# MIPI-Bridge.net
KiCad netlist of a schematic drawn in Altium Designer
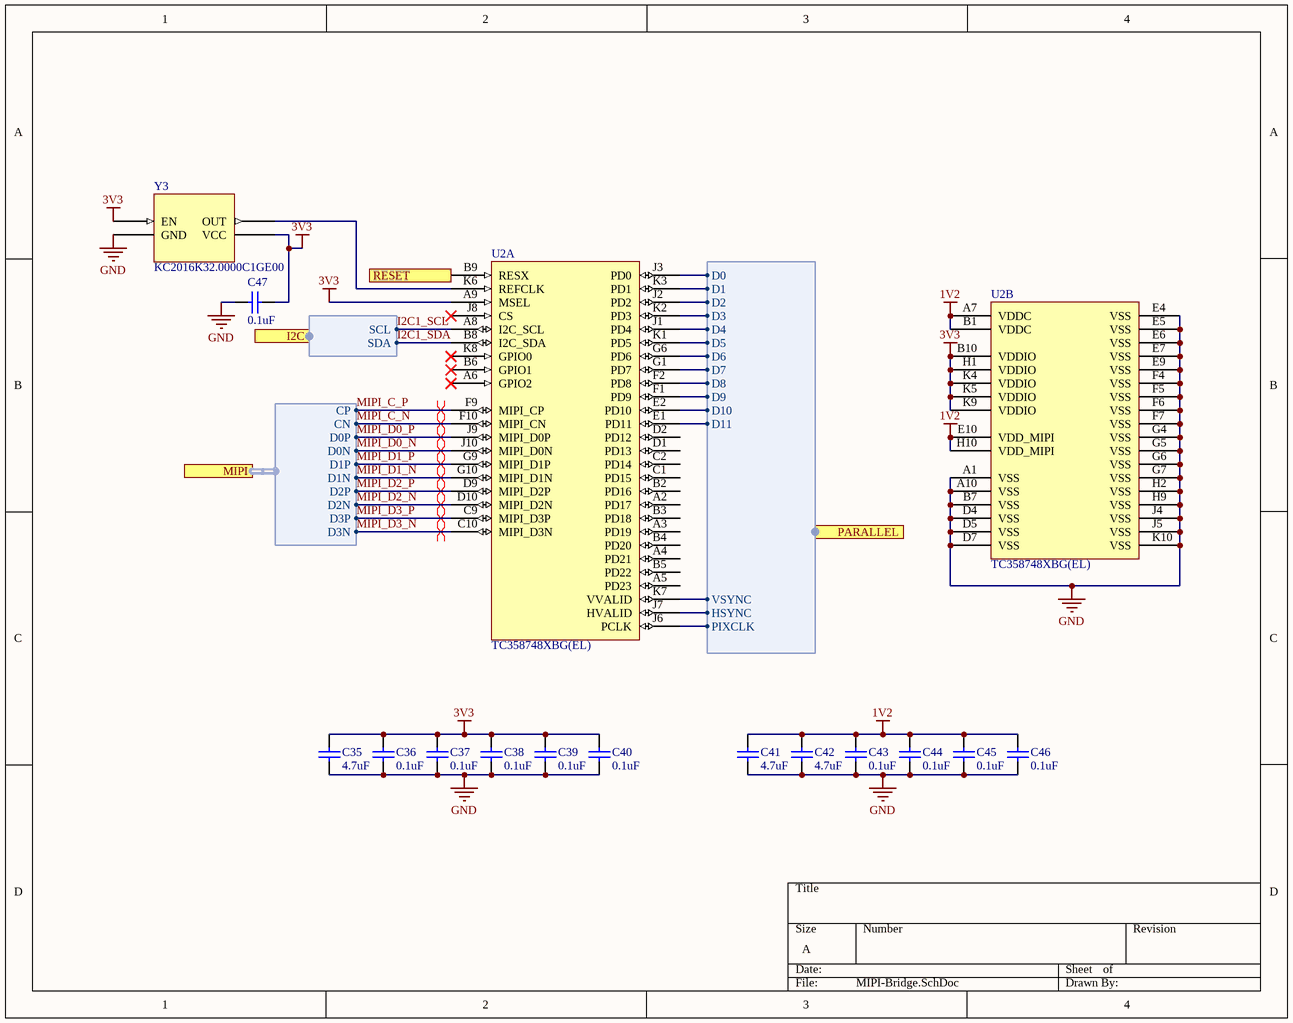
[diagram p0: MIPI-Bridge.SchDoc]

(export (version "E")
  (design (tool "Eeschema 10.0.6"))
  (components
    (comp (ref "C35")
      (value "4.7uF")
      (footprint "C0402[1005X55]")
      (description "4.7uF 6.3V 20% 0402 (1005 Metric)")
      (fields (field (name "PARTNUMBER") "GRM155R60J475ME47D") (field (name "MANUFACTURER") "Murata"))
      (libsource (lib "Capacitors") (part "CAP_4.7uF_6.3V_0402_20%"))
    )
    (comp (ref "C36")
      (value "0.1uF")
      (footprint "C0402[1005X55]")
      (description "0.1uF 6.3V 10% 0402 (1005 Metric)")
      (fields (field (name "PARTNUMBER") "GRM155R70J104KA01D") (field (name "MANUFACTURER") "Murata"))
      (libsource (lib "Capacitors") (part "CAP_0.1uF_6.3V_0402_10%"))
    )
    (comp (ref "C37")
      (value "0.1uF")
      (footprint "C0402[1005X55]")
      (description "0.1uF 6.3V 10% 0402 (1005 Metric)")
      (fields (field (name "PARTNUMBER") "GRM155R70J104KA01D") (field (name "MANUFACTURER") "Murata"))
      (libsource (lib "Capacitors") (part "CAP_0.1uF_6.3V_0402_10%"))
    )
    (comp (ref "C38")
      (value "0.1uF")
      (footprint "C0402[1005X55]")
      (description "0.1uF 6.3V 10% 0402 (1005 Metric)")
      (fields (field (name "PARTNUMBER") "GRM155R70J104KA01D") (field (name "MANUFACTURER") "Murata"))
      (libsource (lib "Capacitors") (part "CAP_0.1uF_6.3V_0402_10%"))
    )
    (comp (ref "C39")
      (value "0.1uF")
      (footprint "C0402[1005X55]")
      (description "0.1uF 6.3V 10% 0402 (1005 Metric)")
      (fields (field (name "PARTNUMBER") "GRM155R70J104KA01D") (field (name "MANUFACTURER") "Murata"))
      (libsource (lib "Capacitors") (part "CAP_0.1uF_6.3V_0402_10%"))
    )
    (comp (ref "C40")
      (value "0.1uF")
      (footprint "C0402[1005X55]")
      (description "0.1uF 6.3V 10% 0402 (1005 Metric)")
      (fields (field (name "PARTNUMBER") "GRM155R70J104KA01D") (field (name "MANUFACTURER") "Murata"))
      (libsource (lib "Capacitors") (part "CAP_0.1uF_6.3V_0402_10%"))
    )
    (comp (ref "C41")
      (value "4.7uF")
      (footprint "C0402[1005X55]")
      (description "4.7uF 6.3V 20% 0402 (1005 Metric)")
      (fields (field (name "PARTNUMBER") "GRM155R60J475ME47D") (field (name "MANUFACTURER") "Murata"))
      (libsource (lib "Capacitors") (part "CAP_4.7uF_6.3V_0402_20%"))
    )
    (comp (ref "C42")
      (value "4.7uF")
      (footprint "C0402[1005X55]")
      (description "4.7uF 6.3V 20% 0402 (1005 Metric)")
      (fields (field (name "PARTNUMBER") "GRM155R60J475ME47D") (field (name "MANUFACTURER") "Murata"))
      (libsource (lib "Capacitors") (part "CAP_4.7uF_6.3V_0402_20%"))
    )
    (comp (ref "C43")
      (value "0.1uF")
      (footprint "C0402[1005X55]")
      (description "0.1uF 6.3V 10% 0402 (1005 Metric)")
      (fields (field (name "PARTNUMBER") "GRM155R70J104KA01D") (field (name "MANUFACTURER") "Murata"))
      (libsource (lib "Capacitors") (part "CAP_0.1uF_6.3V_0402_10%"))
    )
    (comp (ref "C44")
      (value "0.1uF")
      (footprint "C0402[1005X55]")
      (description "0.1uF 6.3V 10% 0402 (1005 Metric)")
      (fields (field (name "PARTNUMBER") "GRM155R70J104KA01D") (field (name "MANUFACTURER") "Murata"))
      (libsource (lib "Capacitors") (part "CAP_0.1uF_6.3V_0402_10%"))
    )
    (comp (ref "C45")
      (value "0.1uF")
      (footprint "C0402[1005X55]")
      (description "0.1uF 6.3V 10% 0402 (1005 Metric)")
      (fields (field (name "PARTNUMBER") "GRM155R70J104KA01D") (field (name "MANUFACTURER") "Murata"))
      (libsource (lib "Capacitors") (part "CAP_0.1uF_6.3V_0402_10%"))
    )
    (comp (ref "C46")
      (value "0.1uF")
      (footprint "C0402[1005X55]")
      (description "0.1uF 6.3V 10% 0402 (1005 Metric)")
      (fields (field (name "PARTNUMBER") "GRM155R70J104KA01D") (field (name "MANUFACTURER") "Murata"))
      (libsource (lib "Capacitors") (part "CAP_0.1uF_6.3V_0402_10%"))
    )
    (comp (ref "C47")
      (value "0.1uF")
      (footprint "C0402[1005X55]")
      (description "0.1uF 6.3V 10% 0402 (1005 Metric)")
      (fields (field (name "PARTNUMBER") "GRM155R70J104KA01D") (field (name "MANUFACTURER") "Murata"))
      (libsource (lib "Capacitors") (part "CAP_0.1uF_6.3V_0402_10%"))
    )
    (comp (ref "U2")
      (value "TC358748XBG(EL)")
      (footprint "BGA-80")
      (description "IC MIPI CSI2 TO PARALLEL 80VFBGA")
      (fields (field (name "MANUFACTURER") "Toshiba Semiconductor"))
      (libsource (lib "ICs") (part "TC358748XBG(EL)"))
    )
    (comp (ref "Y3")
      (value "KC2016K32.0000C1GE00")
      (footprint "KC2016K")
      (description "OSC XO 32.0000MHZ CMOS SMD")
      (fields (field (name "MANUFACTURER") "Kyocera"))
      (libsource (lib "Components") (part "KC2016K32.0000C1GE00"))
    )
  )
  (nets
    (net (code "4") (name "/D0") (class "Default")
      (node (ref "U2") (pin "J3") (pinfunction "PD0_J3") (pintype "bidirectional"))
    )
    (net (code "5") (name "/D1") (class "Default")
      (node (ref "U2") (pin "K3") (pinfunction "PD1_K3") (pintype "bidirectional"))
    )
    (net (code "6") (name "/D2") (class "Default")
      (node (ref "U2") (pin "J2") (pinfunction "PD2_J2") (pintype "bidirectional"))
    )
    (net (code "7") (name "/D3") (class "Default")
      (node (ref "U2") (pin "K2") (pinfunction "PD3_K2") (pintype "bidirectional"))
    )
    (net (code "8") (name "/D4") (class "Default")
      (node (ref "U2") (pin "J1") (pinfunction "PD4_J1") (pintype "bidirectional"))
    )
    (net (code "9") (name "/D5") (class "Default")
      (node (ref "U2") (pin "K1") (pinfunction "PD5_K1") (pintype "bidirectional"))
    )
    (net (code "10") (name "/D6") (class "Default")
      (node (ref "U2") (pin "G6") (pinfunction "PD6_G6") (pintype "bidirectional"))
    )
    (net (code "11") (name "/D7") (class "Default")
      (node (ref "U2") (pin "G1") (pinfunction "PD7_G1") (pintype "bidirectional"))
    )
    (net (code "12") (name "/D8") (class "Default")
      (node (ref "U2") (pin "F2") (pinfunction "PD8_F2") (pintype "bidirectional"))
    )
    (net (code "13") (name "/D9") (class "Default")
      (node (ref "U2") (pin "F1") (pinfunction "PD9_F1") (pintype "bidirectional"))
    )
    (net (code "14") (name "/D10") (class "Default")
      (node (ref "U2") (pin "E2") (pinfunction "PD10_E2") (pintype "bidirectional"))
    )
    (net (code "15") (name "/D11") (class "Default")
      (node (ref "U2") (pin "E1") (pinfunction "PD11_E1") (pintype "bidirectional"))
    )
    (net (code "16") (name "/HSYNC") (class "Default")
      (node (ref "U2") (pin "J7") (pinfunction "HVALID_J7") (pintype "bidirectional"))
    )
    (net (code "17") (name "/I2C1_SCL") (class "Default")
      (node (ref "U2") (pin "A8") (pinfunction "I2C_SCL_A8") (pintype "bidirectional"))
    )
    (net (code "18") (name "/I2C1_SDA") (class "Default")
      (node (ref "U2") (pin "B8") (pinfunction "I2C_SDA_B8") (pintype "bidirectional"))
    )
    (net (code "19") (name "/MIPI_C_N") (class "Default")
      (node (ref "U2") (pin "F10") (pinfunction "MIPI_CN_F10") (pintype "bidirectional"))
    )
    (net (code "20") (name "/MIPI_C_P") (class "Default")
      (node (ref "U2") (pin "F9") (pinfunction "MIPI_CP_F9") (pintype "bidirectional"))
    )
    (net (code "21") (name "/MIPI_D0_N") (class "Default")
      (node (ref "U2") (pin "J10") (pinfunction "MIPI_D0N_J10") (pintype "bidirectional"))
    )
    (net (code "22") (name "/MIPI_D0_P") (class "Default")
      (node (ref "U2") (pin "J9") (pinfunction "MIPI_D0P_J9") (pintype "bidirectional"))
    )
    (net (code "23") (name "/MIPI_D1_N") (class "Default")
      (node (ref "U2") (pin "G10") (pinfunction "MIPI_D1N_G10") (pintype "bidirectional"))
    )
    (net (code "24") (name "/MIPI_D1_P") (class "Default")
      (node (ref "U2") (pin "G9") (pinfunction "MIPI_D1P_G9") (pintype "bidirectional"))
    )
    (net (code "25") (name "/MIPI_D2_N") (class "Default")
      (node (ref "U2") (pin "D10") (pinfunction "MIPI_D2N_D10") (pintype "bidirectional"))
    )
    (net (code "26") (name "/MIPI_D2_P") (class "Default")
      (node (ref "U2") (pin "D9") (pinfunction "MIPI_D2P_D9") (pintype "bidirectional"))
    )
    (net (code "27") (name "/MIPI_D3_N") (class "Default")
      (node (ref "U2") (pin "C10") (pinfunction "MIPI_D3N_C10") (pintype "bidirectional"))
    )
    (net (code "28") (name "/MIPI_D3_P") (class "Default")
      (node (ref "U2") (pin "C9") (pinfunction "MIPI_D3P_C9") (pintype "bidirectional"))
    )
    (net (code "29") (name "/PIXCLK") (class "Default")
      (node (ref "U2") (pin "J6") (pinfunction "PCLK_J6") (pintype "bidirectional"))
    )
    (net (code "30") (name "/RESET") (class "Default")
      (node (ref "U2") (pin "B9") (pinfunction "RESX_B9") (pintype "input"))
    )
    (net (code "31") (name "/VSYNC") (class "Default")
      (node (ref "U2") (pin "K7") (pinfunction "VVALID_K7") (pintype "bidirectional"))
    )
    (net (code "35") (name "1V2") (class "Default")
      (node (ref "C41") (pin "2") (pinfunction "2_2") (pintype "passive"))
      (node (ref "C42") (pin "2") (pinfunction "2_2") (pintype "passive"))
      (node (ref "C43") (pin "2") (pinfunction "2_2") (pintype "passive"))
      (node (ref "C44") (pin "2") (pinfunction "2_2") (pintype "passive"))
      (node (ref "C45") (pin "2") (pinfunction "2_2") (pintype "passive"))
      (node (ref "C46") (pin "2") (pinfunction "2_2") (pintype "passive"))
      (node (ref "U2") (pin "A7") (pinfunction "VDDC_A7") (pintype "power_in"))
      (node (ref "U2") (pin "B1") (pinfunction "VDDC_B1") (pintype "power_in"))
      (node (ref "U2") (pin "E10") (pinfunction "VDD_MIPI_E10") (pintype "power_in"))
      (node (ref "U2") (pin "H10") (pinfunction "VDD_MIPI_H10") (pintype "power_in"))
    )
    (net (code "36") (name "3V3") (class "Default")
      (node (ref "C35") (pin "2") (pinfunction "2_2") (pintype "passive"))
      (node (ref "C36") (pin "2") (pinfunction "2_2") (pintype "passive"))
      (node (ref "C37") (pin "2") (pinfunction "2_2") (pintype "passive"))
      (node (ref "C38") (pin "2") (pinfunction "2_2") (pintype "passive"))
      (node (ref "C39") (pin "2") (pinfunction "2_2") (pintype "passive"))
      (node (ref "C40") (pin "2") (pinfunction "2_2") (pintype "passive"))
      (node (ref "C47") (pin "1") (pinfunction "1_1") (pintype "passive"))
      (node (ref "U2") (pin "A9") (pinfunction "MSEL_A9") (pintype "input"))
      (node (ref "U2") (pin "B10") (pinfunction "VDDIO_B10") (pintype "power_in"))
      (node (ref "U2") (pin "H1") (pinfunction "VDDIO_H1") (pintype "power_in"))
      (node (ref "U2") (pin "K4") (pinfunction "VDDIO_K4") (pintype "power_in"))
      (node (ref "U2") (pin "K5") (pinfunction "VDDIO_K5") (pintype "power_in"))
      (node (ref "U2") (pin "K9") (pinfunction "VDDIO_K9") (pintype "power_in"))
      (node (ref "Y3") (pin "1") (pinfunction "EN_1") (pintype "input"))
      (node (ref "Y3") (pin "4") (pinfunction "VCC_4") (pintype "power_in"))
    )
    (net (code "37") (name "GND") (class "Default")
      (node (ref "C35") (pin "1") (pinfunction "1_1") (pintype "passive"))
      (node (ref "C36") (pin "1") (pinfunction "1_1") (pintype "passive"))
      (node (ref "C37") (pin "1") (pinfunction "1_1") (pintype "passive"))
      (node (ref "C38") (pin "1") (pinfunction "1_1") (pintype "passive"))
      (node (ref "C39") (pin "1") (pinfunction "1_1") (pintype "passive"))
      (node (ref "C40") (pin "1") (pinfunction "1_1") (pintype "passive"))
      (node (ref "C41") (pin "1") (pinfunction "1_1") (pintype "passive"))
      (node (ref "C42") (pin "1") (pinfunction "1_1") (pintype "passive"))
      (node (ref "C43") (pin "1") (pinfunction "1_1") (pintype "passive"))
      (node (ref "C44") (pin "1") (pinfunction "1_1") (pintype "passive"))
      (node (ref "C45") (pin "1") (pinfunction "1_1") (pintype "passive"))
      (node (ref "C46") (pin "1") (pinfunction "1_1") (pintype "passive"))
      (node (ref "C47") (pin "2") (pinfunction "2_2") (pintype "passive"))
      (node (ref "U2") (pin "A1") (pinfunction "VSS_A1") (pintype "power_in"))
      (node (ref "U2") (pin "A10") (pinfunction "VSS_A10") (pintype "power_in"))
      (node (ref "U2") (pin "B7") (pinfunction "VSS_B7") (pintype "power_in"))
      (node (ref "U2") (pin "D4") (pinfunction "VSS_D4") (pintype "power_in"))
      (node (ref "U2") (pin "D5") (pinfunction "VSS_D5") (pintype "power_in"))
      (node (ref "U2") (pin "D7") (pinfunction "VSS_D7") (pintype "power_in"))
      (node (ref "U2") (pin "E4") (pinfunction "VSS_E4") (pintype "power_in"))
      (node (ref "U2") (pin "E5") (pinfunction "VSS_E5") (pintype "power_in"))
      (node (ref "U2") (pin "E6") (pinfunction "VSS_E6") (pintype "power_in"))
      (node (ref "U2") (pin "E7") (pinfunction "VSS_E7") (pintype "power_in"))
      (node (ref "U2") (pin "E9") (pinfunction "VSS_E9") (pintype "power_in"))
      (node (ref "U2") (pin "F4") (pinfunction "VSS_F4") (pintype "power_in"))
      (node (ref "U2") (pin "F5") (pinfunction "VSS_F5") (pintype "power_in"))
      (node (ref "U2") (pin "F6") (pinfunction "VSS_F6") (pintype "power_in"))
      (node (ref "U2") (pin "F7") (pinfunction "VSS_F7") (pintype "power_in"))
      (node (ref "U2") (pin "G4") (pinfunction "VSS_G4") (pintype "power_in"))
      (node (ref "U2") (pin "G5") (pinfunction "VSS_G5") (pintype "power_in"))
      (node (ref "U2") (pin "G6") (pinfunction "VSS_G6") (pintype "power_in"))
      (node (ref "U2") (pin "G7") (pinfunction "VSS_G7") (pintype "power_in"))
      (node (ref "U2") (pin "H2") (pinfunction "VSS_H2") (pintype "power_in"))
      (node (ref "U2") (pin "H9") (pinfunction "VSS_H9") (pintype "power_in"))
      (node (ref "U2") (pin "J4") (pinfunction "VSS_J4") (pintype "power_in"))
      (node (ref "U2") (pin "J5") (pinfunction "VSS_J5") (pintype "power_in"))
      (node (ref "U2") (pin "K10") (pinfunction "VSS_K10") (pintype "power_in"))
      (node (ref "Y3") (pin "2") (pinfunction "GND_2") (pintype "power_in"))
    )
    (net (code "38") (name "Net-(U2A-REFCLK)") (class "Default")
      (node (ref "U2") (pin "K6") (pinfunction "REFCLK_K6") (pintype "input"))
      (node (ref "Y3") (pin "3") (pinfunction "OUT_3") (pintype "output"))
    )
    (net (code "39") (name "unconnected-(U2A-CS-PadJ8)") (class "Default")
      (node (ref "U2") (pin "J8") (pinfunction "CS_J8") (pintype "input+no_connect"))
    )
    (net (code "40") (name "unconnected-(U2A-GPIO0-PadK8)") (class "Default")
      (node (ref "U2") (pin "K8") (pinfunction "GPIO0_K8") (pintype "input+no_connect"))
    )
    (net (code "41") (name "unconnected-(U2A-GPIO1-PadB6)") (class "Default")
      (node (ref "U2") (pin "B6") (pinfunction "GPIO1_B6") (pintype "input+no_connect"))
    )
    (net (code "42") (name "unconnected-(U2A-GPIO2-PadA6)") (class "Default")
      (node (ref "U2") (pin "A6") (pinfunction "GPIO2_A6") (pintype "input+no_connect"))
    )
    (net (code "43") (name "unconnected-(U2A-PD12-PadD2)") (class "Default")
      (node (ref "U2") (pin "D2") (pinfunction "PD12_D2") (pintype "bidirectional"))
    )
    (net (code "44") (name "unconnected-(U2A-PD13-PadD1)") (class "Default")
      (node (ref "U2") (pin "D1") (pinfunction "PD13_D1") (pintype "bidirectional"))
    )
    (net (code "45") (name "unconnected-(U2A-PD14-PadC2)") (class "Default")
      (node (ref "U2") (pin "C2") (pinfunction "PD14_C2") (pintype "bidirectional"))
    )
    (net (code "46") (name "unconnected-(U2A-PD15-PadC1)") (class "Default")
      (node (ref "U2") (pin "C1") (pinfunction "PD15_C1") (pintype "bidirectional"))
    )
    (net (code "47") (name "unconnected-(U2A-PD16-PadB2)") (class "Default")
      (node (ref "U2") (pin "B2") (pinfunction "PD16_B2") (pintype "bidirectional"))
    )
    (net (code "48") (name "unconnected-(U2A-PD17-PadA2)") (class "Default")
      (node (ref "U2") (pin "A2") (pinfunction "PD17_A2") (pintype "bidirectional"))
    )
    (net (code "49") (name "unconnected-(U2A-PD18-PadB3)") (class "Default")
      (node (ref "U2") (pin "B3") (pinfunction "PD18_B3") (pintype "bidirectional"))
    )
    (net (code "50") (name "unconnected-(U2A-PD19-PadA3)") (class "Default")
      (node (ref "U2") (pin "A3") (pinfunction "PD19_A3") (pintype "bidirectional"))
    )
    (net (code "51") (name "unconnected-(U2A-PD20-PadB4)") (class "Default")
      (node (ref "U2") (pin "B4") (pinfunction "PD20_B4") (pintype "bidirectional"))
    )
    (net (code "52") (name "unconnected-(U2A-PD21-PadA4)") (class "Default")
      (node (ref "U2") (pin "A4") (pinfunction "PD21_A4") (pintype "bidirectional"))
    )
    (net (code "53") (name "unconnected-(U2A-PD22-PadB5)") (class "Default")
      (node (ref "U2") (pin "B5") (pinfunction "PD22_B5") (pintype "bidirectional"))
    )
    (net (code "54") (name "unconnected-(U2A-PD23-PadA5)") (class "Default")
      (node (ref "U2") (pin "A5") (pinfunction "PD23_A5") (pintype "bidirectional"))
    )
  )
)
